# DK_STM32L151.net
KiCad netlist of a schematic drawn in Altium Designer
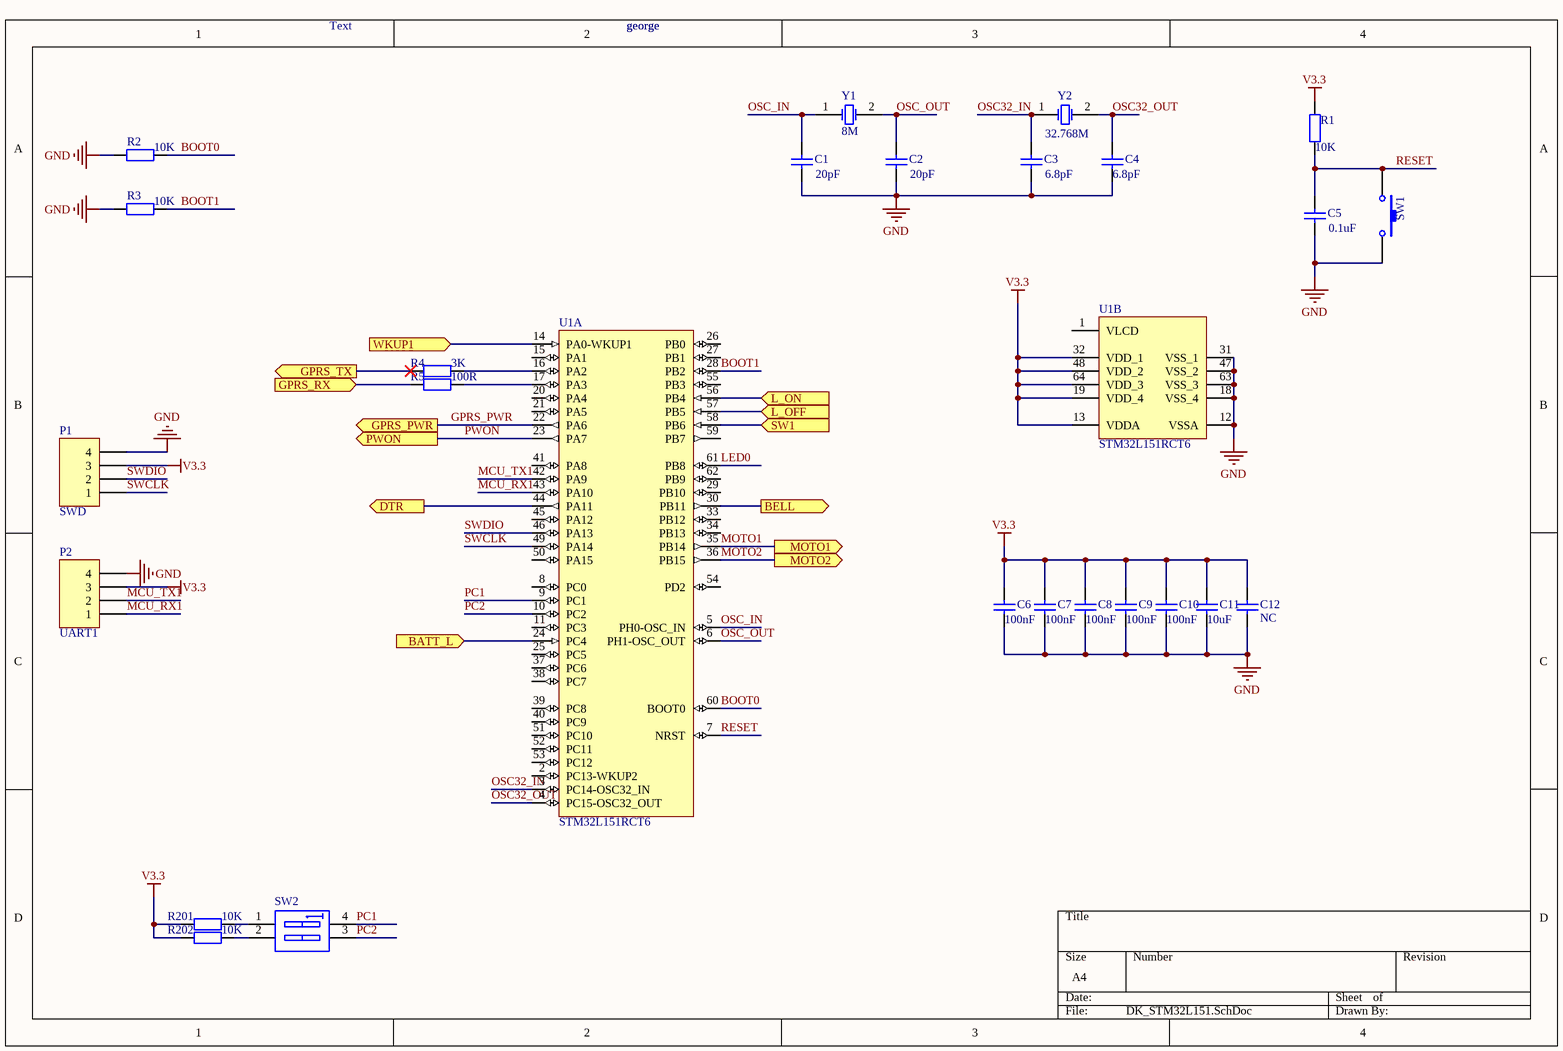
[diagram p0: DK_STM32L151.SchDoc]

(export (version "E")
  (design (tool "Eeschema 10.0.6"))
  (components
    (comp (ref "C1")
      (value "20pF")
      (footprint "0603")
      (description "Capacitor")
      (fields (field (name "Comment") "Cap") (field (name "PUBLISHER") "Altium Limited"))
      (libsource (lib "Miscellaneous Devices") (part "Cap"))
    )
    (comp (ref "C2")
      (value "20pF")
      (footprint "0603")
      (description "Capacitor")
      (fields (field (name "Comment") "Cap") (field (name "PUBLISHER") "Altium Limited"))
      (libsource (lib "Miscellaneous Devices") (part "Cap"))
    )
    (comp (ref "C3")
      (value "6.8pF")
      (footprint "0603")
      (description "Capacitor")
      (fields (field (name "Comment") "Cap") (field (name "PUBLISHER") "Altium Limited"))
      (libsource (lib "Miscellaneous Devices") (part "Cap"))
    )
    (comp (ref "C4")
      (value "6.8pF")
      (footprint "0603")
      (description "Capacitor")
      (fields (field (name "Comment") "Cap") (field (name "PUBLISHER") "Altium Limited"))
      (libsource (lib "Miscellaneous Devices") (part "Cap"))
    )
    (comp (ref "C5")
      (value "0.1uF")
      (footprint "0603")
      (description "Capacitor")
      (fields (field (name "Comment") "Cap") (field (name "PUBLISHER") "Altium Limited"))
      (libsource (lib "Miscellaneous Devices") (part "Cap"))
    )
    (comp (ref "C6")
      (value "100nF")
      (footprint "0603")
      (description "Capacitor")
      (fields (field (name "Comment") "Cap") (field (name "PUBLISHER") "Altium Limited"))
      (libsource (lib "Miscellaneous Devices") (part "Cap"))
    )
    (comp (ref "C7")
      (value "100nF")
      (footprint "0603")
      (description "Capacitor")
      (fields (field (name "Comment") "Cap") (field (name "PUBLISHER") "Altium Limited"))
      (libsource (lib "Miscellaneous Devices") (part "Cap"))
    )
    (comp (ref "C8")
      (value "100nF")
      (footprint "0603")
      (description "Capacitor")
      (fields (field (name "Comment") "Cap") (field (name "PUBLISHER") "Altium Limited"))
      (libsource (lib "Miscellaneous Devices") (part "Cap"))
    )
    (comp (ref "C9")
      (value "100nF")
      (footprint "0603")
      (description "Capacitor")
      (fields (field (name "Comment") "Cap") (field (name "PUBLISHER") "Altium Limited"))
      (libsource (lib "Miscellaneous Devices") (part "Cap"))
    )
    (comp (ref "C10")
      (value "100nF")
      (footprint "1206")
      (description "Capacitor")
      (fields (field (name "Comment") "Cap") (field (name "PUBLISHER") "Altium Limited"))
      (libsource (lib "Miscellaneous Devices") (part "Cap"))
    )
    (comp (ref "C11")
      (value "10uF")
      (footprint "LC-CASE-A_3216")
      (description "Capacitor")
      (fields (field (name "Comment") "Cap") (field (name "PUBLISHER") "Altium Limited"))
      (libsource (lib "Miscellaneous Devices") (part "Cap"))
    )
    (comp (ref "C12")
      (value "NC")
      (footprint "0603")
      (description "Capacitor")
      (fields (field (name "PUBLISHER") "Altium Limited"))
      (libsource (lib "Miscellaneous Devices") (part "Cap"))
    )
    (comp (ref "P1")
      (value "SWD")
      (footprint "HDR1X4")
      (description "Header, 4-Pin")
      (fields (field (name "PUBLISHER") "Altium Limited"))
      (libsource (lib "Miscellaneous Connectors") (part "Header 4"))
    )
    (comp (ref "P2")
      (value "UART1")
      (footprint "HDR1X4")
      (description "Header, 4-Pin")
      (fields (field (name "PUBLISHER") "Altium Limited"))
      (libsource (lib "Miscellaneous Connectors") (part "Header 4"))
    )
    (comp (ref "R1")
      (value "10K")
      (footprint "0603")
      (description "Resistor")
      (fields (field (name "Comment") "Res2") (field (name "PUBLISHER") "Altium Limited"))
      (libsource (lib "") (part "Res2_1"))
    )
    (comp (ref "R2")
      (value "10K")
      (footprint "0603")
      (description "Resistor")
      (fields (field (name "Comment") "Res2") (field (name "PUBLISHER") "Altium Limited"))
      (libsource (lib "Miscellaneous Devices") (part "Res2"))
    )
    (comp (ref "R3")
      (value "10K")
      (footprint "0603")
      (description "Resistor")
      (fields (field (name "Comment") "Res2") (field (name "PUBLISHER") "Altium Limited"))
      (libsource (lib "Miscellaneous Devices") (part "Res2"))
    )
    (comp (ref "R4")
      (value "3K")
      (footprint "0603")
      (description "Resistor")
      (fields (field (name "Comment") "Res2") (field (name "PUBLISHER") "Altium Limited"))
      (libsource (lib "Miscellaneous Devices") (part "Res2"))
    )
    (comp (ref "R5")
      (value "100R")
      (footprint "0603")
      (description "Resistor")
      (fields (field (name "Comment") "Res2") (field (name "PUBLISHER") "Altium Limited"))
      (libsource (lib "Miscellaneous Devices") (part "Res2"))
    )
    (comp (ref "R201")
      (value "10K")
      (footprint "0603")
      (description "Resistor")
      (fields (field (name "Comment") "Res2") (field (name "PUBLISHER") "Altium Limited"))
      (libsource (lib "Miscellaneous Devices") (part "Res2"))
    )
    (comp (ref "R202")
      (value "10K")
      (footprint "0603")
      (description "Resistor")
      (fields (field (name "Comment") "Res2") (field (name "PUBLISHER") "Altium Limited"))
      (libsource (lib "Miscellaneous Devices") (part "Res2"))
    )
    (comp (ref "SW1")
      (value "SW-PB")
      (footprint "3*6*4.3")
      (description "Switch")
      (fields (field (name "PUBLISHER") "Altium Limited"))
      (libsource (lib "Miscellaneous Devices") (part "SW-PB"))
    )
    (comp (ref "SW2")
      (value "SW DIP-2")
      (footprint "SW-2*4")
      (description "DIP Switch, 2 Position, SPST")
      (fields (field (name "PUBLISHER") "Altium Limited"))
      (libsource (lib "Miscellaneous Devices") (part "SW DIP-2"))
    )
    (comp (ref "U1")
      (value "STM32L151RCT6")
      (footprint "LQFP64")
      (fields (field (name "MANUFACTURER") "STMicroelectronics"))
      (libsource (lib "STMicroelectronics STM32 L1") (part "STM32L151RCT6"))
    )
    (comp (ref "Y1")
      (value "8M")
      (footprint "SMT-OSC")
      (description "Crystal Oscillator")
      (fields (field (name "PUBLISHER") "Altium Limited"))
      (libsource (lib "Miscellaneous Devices") (part "XTAL"))
    )
    (comp (ref "Y2")
      (value "32.768M")
      (footprint "XTAL32.786")
      (description "Crystal Oscillator")
      (fields (field (name "PUBLISHER") "Altium Limited"))
      (libsource (lib "Miscellaneous Devices") (part "XTAL"))
    )
  )
  (nets
    (net (code "1") (name "/BATT_L") (class "Default")
      (node (ref "U1") (pin "24") (pinfunction "PC4_24") (pintype "input"))
    )
    (net (code "2") (name "/BELL") (class "Default")
      (node (ref "U1") (pin "30") (pinfunction "PB11_30") (pintype "output"))
    )
    (net (code "3") (name "/BOOT0") (class "Default")
      (node (ref "R2") (pin "2") (pinfunction "2_2") (pintype "passive"))
      (node (ref "U1") (pin "60") (pinfunction "BOOT0_60") (pintype "bidirectional"))
    )
    (net (code "4") (name "/BOOT1") (class "Default")
      (node (ref "R3") (pin "2") (pinfunction "2_2") (pintype "passive"))
      (node (ref "U1") (pin "28") (pinfunction "PB2_28") (pintype "bidirectional"))
    )
    (net (code "5") (name "/DTR") (class "Default")
      (node (ref "U1") (pin "44") (pinfunction "PA11_44") (pintype "output"))
    )
    (net (code "6") (name "/GPRS_PWR") (class "Default")
      (node (ref "U1") (pin "22") (pinfunction "PA6_22") (pintype "output"))
    )
    (net (code "7") (name "/GPRS_RX") (class "Default")
      (node (ref "R5") (pin "1") (pinfunction "1_1") (pintype "passive"))
    )
    (net (code "8") (name "/GPRS_TX") (class "Default")
      (node (ref "R4") (pin "1") (pinfunction "1_1") (pintype "passive+no_connect"))
    )
    (net (code "9") (name "/LED0") (class "Default")
      (node (ref "U1") (pin "61") (pinfunction "PB8_61") (pintype "bidirectional"))
    )
    (net (code "10") (name "/L_OFF") (class "Default")
      (node (ref "U1") (pin "57") (pinfunction "PB5_57") (pintype "input"))
    )
    (net (code "11") (name "/L_ON") (class "Default")
      (node (ref "U1") (pin "56") (pinfunction "PB4_56") (pintype "input"))
    )
    (net (code "12") (name "/MCU_RX1") (class "Default")
      (node (ref "P2") (pin "1") (pinfunction "1_1") (pintype "passive"))
      (node (ref "U1") (pin "43") (pinfunction "PA10_43") (pintype "bidirectional"))
    )
    (net (code "13") (name "/MCU_TX1") (class "Default")
      (node (ref "P2") (pin "2") (pinfunction "2_2") (pintype "passive"))
      (node (ref "U1") (pin "42") (pinfunction "PA9_42") (pintype "bidirectional"))
    )
    (net (code "14") (name "/MOTO1") (class "Default")
      (node (ref "U1") (pin "35") (pinfunction "PB14_35") (pintype "output"))
    )
    (net (code "15") (name "/MOTO2") (class "Default")
      (node (ref "U1") (pin "36") (pinfunction "PB15_36") (pintype "output"))
    )
    (net (code "16") (name "/OSC32_IN") (class "Default")
      (node (ref "C3") (pin "2") (pinfunction "2_2") (pintype "passive"))
      (node (ref "U1") (pin "3") (pinfunction "PC14-OSC32_IN_3") (pintype "bidirectional"))
      (node (ref "Y2") (pin "1") (pinfunction "OSC1_1") (pintype "passive"))
    )
    (net (code "17") (name "/OSC32_OUT") (class "Default")
      (node (ref "C4") (pin "2") (pinfunction "2_2") (pintype "passive"))
      (node (ref "U1") (pin "4") (pinfunction "PC15-OSC32_OUT_4") (pintype "bidirectional"))
      (node (ref "Y2") (pin "2") (pinfunction "OSC2_2") (pintype "passive"))
    )
    (net (code "18") (name "/OSC_IN") (class "Default")
      (node (ref "C1") (pin "2") (pinfunction "2_2") (pintype "passive"))
      (node (ref "U1") (pin "5") (pinfunction "PH0-OSC_IN_5") (pintype "bidirectional"))
      (node (ref "Y1") (pin "1") (pinfunction "OSC1_1") (pintype "passive"))
    )
    (net (code "19") (name "/OSC_OUT") (class "Default")
      (node (ref "C2") (pin "2") (pinfunction "2_2") (pintype "passive"))
      (node (ref "U1") (pin "6") (pinfunction "PH1-OSC_OUT_6") (pintype "bidirectional"))
      (node (ref "Y1") (pin "2") (pinfunction "OSC2_2") (pintype "passive"))
    )
    (net (code "20") (name "/PC1") (class "Default")
      (node (ref "SW2") (pin "4") (pinfunction "B1_4") (pintype "passive"))
      (node (ref "U1") (pin "9") (pinfunction "PC1_9") (pintype "bidirectional"))
    )
    (net (code "21") (name "/PC2") (class "Default")
      (node (ref "SW2") (pin "3") (pinfunction "B2_3") (pintype "passive"))
      (node (ref "U1") (pin "10") (pinfunction "PC2_10") (pintype "bidirectional"))
    )
    (net (code "22") (name "/PWON") (class "Default")
      (node (ref "U1") (pin "23") (pinfunction "PA7_23") (pintype "output"))
    )
    (net (code "23") (name "/RESET") (class "Default")
      (node (ref "C5") (pin "1") (pinfunction "1_1") (pintype "passive"))
      (node (ref "R1") (pin "2") (pinfunction "2_2") (pintype "passive"))
      (node (ref "SW1") (pin "1") (pinfunction "1_1") (pintype "passive"))
      (node (ref "U1") (pin "7") (pinfunction "NRST_7") (pintype "bidirectional"))
    )
    (net (code "24") (name "/SW1") (class "Default")
      (node (ref "U1") (pin "58") (pinfunction "PB6_58") (pintype "input"))
    )
    (net (code "25") (name "/SWCLK") (class "Default")
      (node (ref "P1") (pin "1") (pinfunction "1_1") (pintype "passive"))
      (node (ref "U1") (pin "49") (pinfunction "PA14_49") (pintype "bidirectional"))
    )
    (net (code "26") (name "/SWDIO") (class "Default")
      (node (ref "P1") (pin "2") (pinfunction "2_2") (pintype "passive"))
      (node (ref "U1") (pin "46") (pinfunction "PA13_46") (pintype "bidirectional"))
    )
    (net (code "27") (name "/WKUP1") (class "Default")
      (node (ref "U1") (pin "14") (pinfunction "PA0-WKUP1_14") (pintype "input"))
    )
    (net (code "28") (name "GND") (class "Default")
      (node (ref "C1") (pin "1") (pinfunction "1_1") (pintype "passive"))
      (node (ref "C10") (pin "1") (pinfunction "1_1") (pintype "passive"))
      (node (ref "C11") (pin "1") (pinfunction "1_1") (pintype "passive"))
      (node (ref "C12") (pin "1") (pinfunction "1_1") (pintype "passive"))
      (node (ref "C2") (pin "1") (pinfunction "1_1") (pintype "passive"))
      (node (ref "C3") (pin "1") (pinfunction "1_1") (pintype "passive"))
      (node (ref "C4") (pin "1") (pinfunction "1_1") (pintype "passive"))
      (node (ref "C5") (pin "2") (pinfunction "2_2") (pintype "passive"))
      (node (ref "C6") (pin "1") (pinfunction "1_1") (pintype "passive"))
      (node (ref "C7") (pin "1") (pinfunction "1_1") (pintype "passive"))
      (node (ref "C8") (pin "1") (pinfunction "1_1") (pintype "passive"))
      (node (ref "C9") (pin "1") (pinfunction "1_1") (pintype "passive"))
      (node (ref "P1") (pin "4") (pinfunction "4_4") (pintype "passive"))
      (node (ref "P2") (pin "4") (pinfunction "4_4") (pintype "passive"))
      (node (ref "R2") (pin "1") (pinfunction "1_1") (pintype "passive"))
      (node (ref "R3") (pin "1") (pinfunction "1_1") (pintype "passive"))
      (node (ref "SW1") (pin "2") (pinfunction "2_2") (pintype "passive"))
      (node (ref "U1") (pin "12") (pinfunction "VSSA_12") (pintype "power_in"))
      (node (ref "U1") (pin "18") (pinfunction "VSS_4_18") (pintype "power_in"))
      (node (ref "U1") (pin "31") (pinfunction "VSS_1_31") (pintype "power_in"))
      (node (ref "U1") (pin "47") (pinfunction "VSS_2_47") (pintype "power_in"))
      (node (ref "U1") (pin "63") (pinfunction "VSS_3_63") (pintype "power_in"))
    )
    (net (code "29") (name "Net-(SW2-A1)") (class "Default")
      (node (ref "R201") (pin "2") (pinfunction "2_2") (pintype "passive"))
      (node (ref "SW2") (pin "1") (pinfunction "A1_1") (pintype "passive"))
    )
    (net (code "30") (name "Net-(SW2-A2)") (class "Default")
      (node (ref "R202") (pin "2") (pinfunction "2_2") (pintype "passive"))
      (node (ref "SW2") (pin "2") (pinfunction "A2_2") (pintype "passive"))
    )
    (net (code "31") (name "Net-(U1A-PA2)") (class "Default")
      (node (ref "R4") (pin "2") (pinfunction "2_2") (pintype "passive"))
      (node (ref "U1") (pin "16") (pinfunction "PA2_16") (pintype "bidirectional"))
    )
    (net (code "32") (name "Net-(U1A-PA3)") (class "Default")
      (node (ref "R5") (pin "2") (pinfunction "2_2") (pintype "passive"))
      (node (ref "U1") (pin "17") (pinfunction "PA3_17") (pintype "bidirectional"))
    )
    (net (code "33") (name "V3.3") (class "Default")
      (node (ref "C10") (pin "2") (pinfunction "2_2") (pintype "passive"))
      (node (ref "C11") (pin "2") (pinfunction "2_2") (pintype "passive"))
      (node (ref "C12") (pin "2") (pinfunction "2_2") (pintype "passive"))
      (node (ref "C6") (pin "2") (pinfunction "2_2") (pintype "passive"))
      (node (ref "C7") (pin "2") (pinfunction "2_2") (pintype "passive"))
      (node (ref "C8") (pin "2") (pinfunction "2_2") (pintype "passive"))
      (node (ref "C9") (pin "2") (pinfunction "2_2") (pintype "passive"))
      (node (ref "P1") (pin "3") (pinfunction "3_3") (pintype "passive"))
      (node (ref "P2") (pin "3") (pinfunction "3_3") (pintype "passive"))
      (node (ref "R1") (pin "1") (pinfunction "1_1") (pintype "passive"))
      (node (ref "R201") (pin "1") (pinfunction "1_1") (pintype "passive"))
      (node (ref "R202") (pin "1") (pinfunction "1_1") (pintype "passive"))
      (node (ref "U1") (pin "13") (pinfunction "VDDA_13") (pintype "power_in"))
      (node (ref "U1") (pin "19") (pinfunction "VDD_4_19") (pintype "power_in"))
      (node (ref "U1") (pin "32") (pinfunction "VDD_1_32") (pintype "power_in"))
      (node (ref "U1") (pin "48") (pinfunction "VDD_2_48") (pintype "power_in"))
      (node (ref "U1") (pin "64") (pinfunction "VDD_3_64") (pintype "power_in"))
    )
    (net (code "34") (name "unconnected-(U1A-PA1-Pad15)") (class "Default")
      (node (ref "U1") (pin "15") (pinfunction "PA1_15") (pintype "bidirectional"))
    )
    (net (code "35") (name "unconnected-(U1A-PA4-Pad20)") (class "Default")
      (node (ref "U1") (pin "20") (pinfunction "PA4_20") (pintype "bidirectional"))
    )
    (net (code "36") (name "unconnected-(U1A-PA5-Pad21)") (class "Default")
      (node (ref "U1") (pin "21") (pinfunction "PA5_21") (pintype "bidirectional"))
    )
    (net (code "37") (name "unconnected-(U1A-PA8-Pad41)") (class "Default")
      (node (ref "U1") (pin "41") (pinfunction "PA8_41") (pintype "bidirectional"))
    )
    (net (code "38") (name "unconnected-(U1A-PA12-Pad45)") (class "Default")
      (node (ref "U1") (pin "45") (pinfunction "PA12_45") (pintype "bidirectional"))
    )
    (net (code "39") (name "unconnected-(U1A-PA15-Pad50)") (class "Default")
      (node (ref "U1") (pin "50") (pinfunction "PA15_50") (pintype "bidirectional"))
    )
    (net (code "40") (name "unconnected-(U1A-PB0-Pad26)") (class "Default")
      (node (ref "U1") (pin "26") (pinfunction "PB0_26") (pintype "bidirectional"))
    )
    (net (code "41") (name "unconnected-(U1A-PB1-Pad27)") (class "Default")
      (node (ref "U1") (pin "27") (pinfunction "PB1_27") (pintype "bidirectional"))
    )
    (net (code "42") (name "unconnected-(U1A-PB3-Pad55)") (class "Default")
      (node (ref "U1") (pin "55") (pinfunction "PB3_55") (pintype "bidirectional"))
    )
    (net (code "43") (name "unconnected-(U1A-PB7-Pad59)") (class "Default")
      (node (ref "U1") (pin "59") (pinfunction "PB7_59") (pintype "output"))
    )
    (net (code "44") (name "unconnected-(U1A-PB9-Pad62)") (class "Default")
      (node (ref "U1") (pin "62") (pinfunction "PB9_62") (pintype "bidirectional"))
    )
    (net (code "45") (name "unconnected-(U1A-PB10-Pad29)") (class "Default")
      (node (ref "U1") (pin "29") (pinfunction "PB10_29") (pintype "bidirectional"))
    )
    (net (code "46") (name "unconnected-(U1A-PB12-Pad33)") (class "Default")
      (node (ref "U1") (pin "33") (pinfunction "PB12_33") (pintype "bidirectional"))
    )
    (net (code "47") (name "unconnected-(U1A-PB13-Pad34)") (class "Default")
      (node (ref "U1") (pin "34") (pinfunction "PB13_34") (pintype "bidirectional"))
    )
    (net (code "48") (name "unconnected-(U1A-PC0-Pad8)") (class "Default")
      (node (ref "U1") (pin "8") (pinfunction "PC0_8") (pintype "bidirectional"))
    )
    (net (code "49") (name "unconnected-(U1A-PC3-Pad11)") (class "Default")
      (node (ref "U1") (pin "11") (pinfunction "PC3_11") (pintype "bidirectional"))
    )
    (net (code "50") (name "unconnected-(U1A-PC5-Pad25)") (class "Default")
      (node (ref "U1") (pin "25") (pinfunction "PC5_25") (pintype "bidirectional"))
    )
    (net (code "51") (name "unconnected-(U1A-PC6-Pad37)") (class "Default")
      (node (ref "U1") (pin "37") (pinfunction "PC6_37") (pintype "bidirectional"))
    )
    (net (code "52") (name "unconnected-(U1A-PC7-Pad38)") (class "Default")
      (node (ref "U1") (pin "38") (pinfunction "PC7_38") (pintype "bidirectional"))
    )
    (net (code "53") (name "unconnected-(U1A-PC8-Pad39)") (class "Default")
      (node (ref "U1") (pin "39") (pinfunction "PC8_39") (pintype "bidirectional"))
    )
    (net (code "54") (name "unconnected-(U1A-PC9-Pad40)") (class "Default")
      (node (ref "U1") (pin "40") (pinfunction "PC9_40") (pintype "bidirectional"))
    )
    (net (code "55") (name "unconnected-(U1A-PC10-Pad51)") (class "Default")
      (node (ref "U1") (pin "51") (pinfunction "PC10_51") (pintype "bidirectional"))
    )
    (net (code "56") (name "unconnected-(U1A-PC11-Pad52)") (class "Default")
      (node (ref "U1") (pin "52") (pinfunction "PC11_52") (pintype "bidirectional"))
    )
    (net (code "57") (name "unconnected-(U1A-PC12-Pad53)") (class "Default")
      (node (ref "U1") (pin "53") (pinfunction "PC12_53") (pintype "bidirectional"))
    )
    (net (code "58") (name "unconnected-(U1A-PC13-WKUP2-Pad2)") (class "Default")
      (node (ref "U1") (pin "2") (pinfunction "PC13-WKUP2_2") (pintype "bidirectional"))
    )
    (net (code "59") (name "unconnected-(U1A-PD2-Pad54)") (class "Default")
      (node (ref "U1") (pin "54") (pinfunction "PD2_54") (pintype "bidirectional"))
    )
    (net (code "60") (name "unconnected-(U1B-VLCD-Pad1)") (class "Default")
      (node (ref "U1") (pin "1") (pinfunction "VLCD_1") (pintype "power_in"))
    )
  )
)
